# NvideaJetsonUSBPage2.net
KiCad netlist of a schematic drawn in Altium Designer
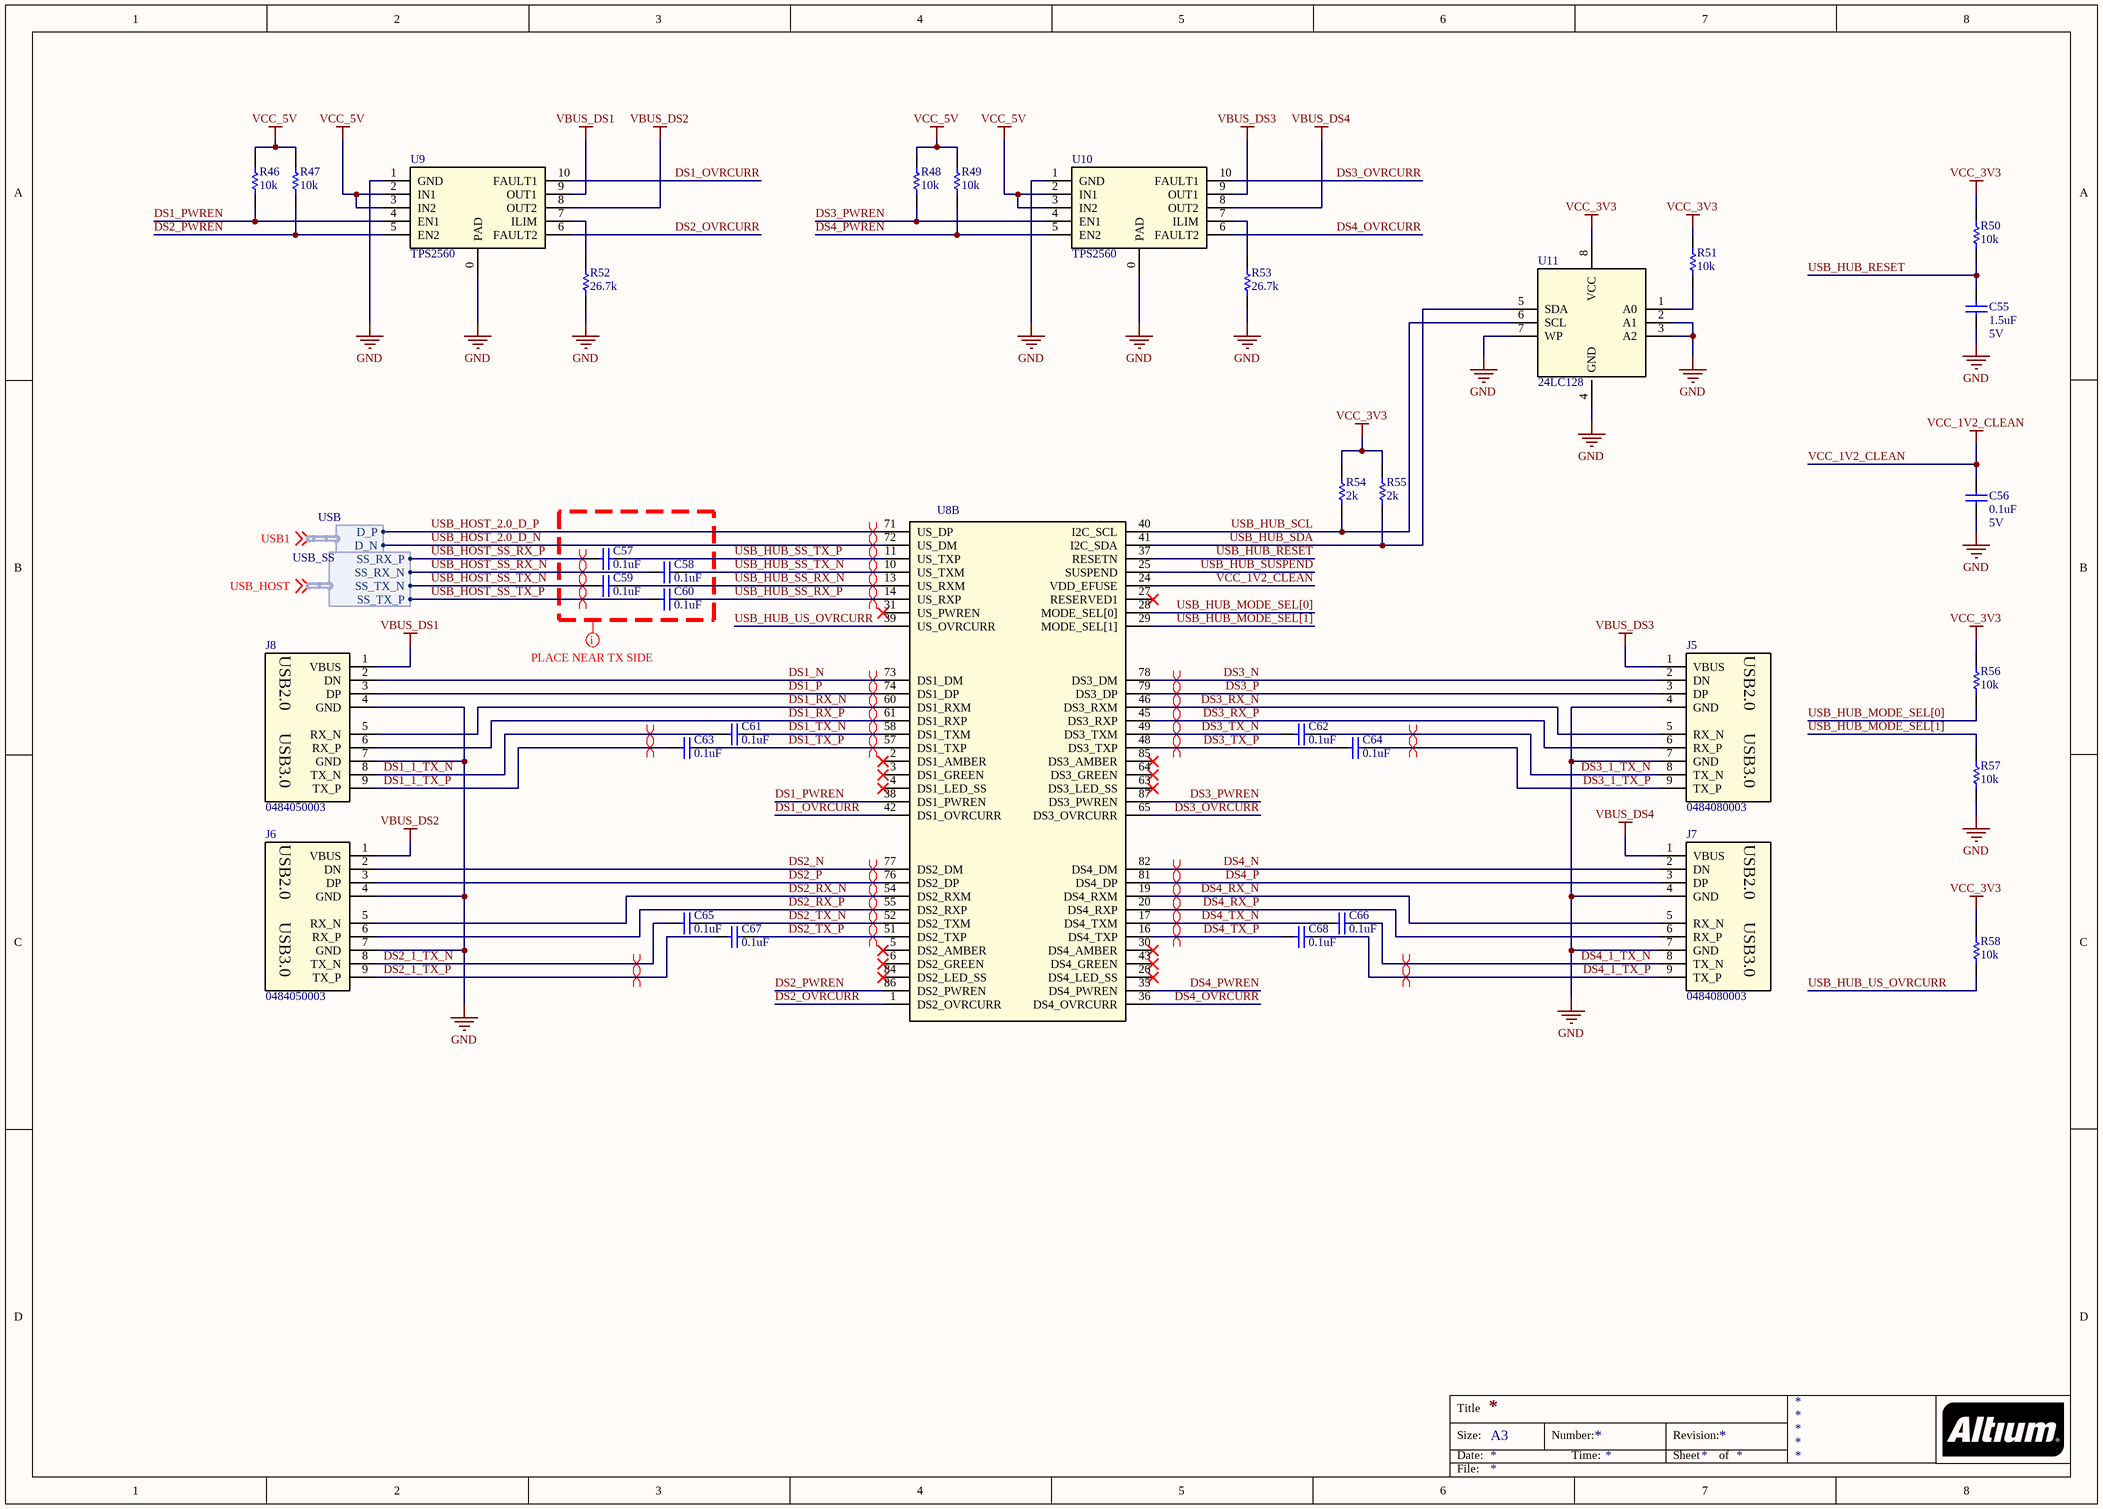
[diagram p0: NvideaJetsonUSBPage2.SchDoc]

(export (version "E")
  (design (tool "Eeschema 10.0.6"))
  (components
    (comp (ref "C55")
      (value "1.5uF")
      (footprint "C0402")
      (description "=Description")
      (fields (field (name "VOLTAGE") "5V") (field (name "Comment") "CAP"))
      (libsource (lib "DRClib") (part "CAP"))
    )
    (comp (ref "C56")
      (value "0.1uF")
      (footprint "C0402")
      (description "=Description")
      (fields (field (name "VOLTAGE") "5V") (field (name "Comment") "CAP"))
      (libsource (lib "DRClib") (part "CAP"))
    )
    (comp (ref "C57")
      (value "0.1uF")
      (footprint "C0402")
      (description "=Description")
      (fields (field (name "Comment") "CAP"))
      (libsource (lib "DRClib") (part "CAP"))
    )
    (comp (ref "C58")
      (value "0.1uF")
      (footprint "C0402")
      (description "=Description")
      (fields (field (name "Comment") "CAP"))
      (libsource (lib "DRClib") (part "CAP"))
    )
    (comp (ref "C59")
      (value "0.1uF")
      (footprint "C0402")
      (description "=Description")
      (fields (field (name "Comment") "CAP"))
      (libsource (lib "DRClib") (part "CAP"))
    )
    (comp (ref "C60")
      (value "0.1uF")
      (footprint "C0402")
      (description "=Description")
      (fields (field (name "Comment") "CAP"))
      (libsource (lib "DRClib") (part "CAP"))
    )
    (comp (ref "C61")
      (value "0.1uF")
      (footprint "C0402")
      (description "=Description")
      (fields (field (name "Comment") "CAP"))
      (libsource (lib "DRClib") (part "CAP"))
    )
    (comp (ref "C62")
      (value "0.1uF")
      (footprint "C0402")
      (description "=Description")
      (fields (field (name "Comment") "CAP"))
      (libsource (lib "DRClib") (part "CAP"))
    )
    (comp (ref "C63")
      (value "0.1uF")
      (footprint "C0402")
      (description "=Description")
      (fields (field (name "Comment") "CAP"))
      (libsource (lib "DRClib") (part "CAP"))
    )
    (comp (ref "C64")
      (value "0.1uF")
      (footprint "C0402")
      (description "=Description")
      (fields (field (name "Comment") "CAP"))
      (libsource (lib "DRClib") (part "CAP"))
    )
    (comp (ref "C65")
      (value "0.1uF")
      (footprint "C0402")
      (description "=Description")
      (fields (field (name "Comment") "CAP"))
      (libsource (lib "DRClib") (part "CAP"))
    )
    (comp (ref "C66")
      (value "0.1uF")
      (footprint "C0402")
      (description "=Description")
      (fields (field (name "Comment") "CAP"))
      (libsource (lib "DRClib") (part "CAP"))
    )
    (comp (ref "C67")
      (value "0.1uF")
      (footprint "C0402")
      (description "=Description")
      (fields (field (name "Comment") "CAP"))
      (libsource (lib "DRClib") (part "CAP"))
    )
    (comp (ref "C68")
      (value "0.1uF")
      (footprint "C0402")
      (description "=Description")
      (fields (field (name "Comment") "CAP"))
      (libsource (lib "DRClib") (part "CAP"))
    )
    (comp (ref "J5")
      (value "0484080003")
      (footprint "0484080003")
      (description "USB3.0 Recepticle Vertical")
      (libsource (lib "DRClib") (part "0484080003"))
    )
    (comp (ref "J6")
      (value "0484050003")
      (footprint "0484050003")
      (description "USB3.0 Recepticle Right Angle")
      (libsource (lib "DRClib") (part "0484050003"))
    )
    (comp (ref "J7")
      (value "0484080003")
      (footprint "0484080003")
      (description "USB3.0 Recepticle Vertical")
      (libsource (lib "DRClib") (part "0484080003"))
    )
    (comp (ref "J8")
      (value "0484050003")
      (footprint "0484050003")
      (description "USB3.0 Recepticle Right Angle")
      (libsource (lib "DRClib") (part "0484050003"))
    )
    (comp (ref "R46")
      (value "10k")
      (footprint "R0402")
      (description "=Description")
      (fields (field (name "Comment") "RES"))
      (libsource (lib "DRClib") (part "RES"))
    )
    (comp (ref "R47")
      (value "10k")
      (footprint "R0402")
      (description "=Description")
      (fields (field (name "Comment") "RES"))
      (libsource (lib "DRClib") (part "RES"))
    )
    (comp (ref "R48")
      (value "10k")
      (footprint "R0402")
      (description "=Description")
      (fields (field (name "Comment") "RES"))
      (libsource (lib "DRClib") (part "RES"))
    )
    (comp (ref "R49")
      (value "10k")
      (footprint "R0402")
      (description "=Description")
      (fields (field (name "Comment") "RES"))
      (libsource (lib "DRClib") (part "RES"))
    )
    (comp (ref "R50")
      (value "10k")
      (footprint "R0402")
      (description "=Description")
      (fields (field (name "Comment") "RES"))
      (libsource (lib "DRClib") (part "RES"))
    )
    (comp (ref "R51")
      (value "10k")
      (footprint "R0402")
      (description "=Description")
      (fields (field (name "Comment") "RES"))
      (libsource (lib "DRClib") (part "RES"))
    )
    (comp (ref "R52")
      (value "26.7k")
      (footprint "R0402")
      (description "=Description")
      (fields (field (name "Comment") "RES"))
      (libsource (lib "DRClib") (part "RES"))
    )
    (comp (ref "R53")
      (value "26.7k")
      (footprint "R0402")
      (description "=Description")
      (fields (field (name "Comment") "RES"))
      (libsource (lib "DRClib") (part "RES"))
    )
    (comp (ref "R54")
      (value "2k")
      (footprint "R0402")
      (description "=Description")
      (fields (field (name "Comment") "RES"))
      (libsource (lib "DRClib") (part "RES"))
    )
    (comp (ref "R55")
      (value "2k")
      (footprint "R0402")
      (description "=Description")
      (fields (field (name "Comment") "RES"))
      (libsource (lib "DRClib") (part "RES"))
    )
    (comp (ref "R56")
      (value "10k")
      (footprint "R0402")
      (description "=Description")
      (fields (field (name "Comment") "RES"))
      (libsource (lib "DRClib") (part "RES"))
    )
    (comp (ref "R57")
      (value "10k")
      (footprint "R0402")
      (description "=Description")
      (fields (field (name "Comment") "RES"))
      (libsource (lib "DRClib") (part "RES"))
    )
    (comp (ref "R58")
      (value "10k")
      (footprint "R0402")
      (description "=Description")
      (fields (field (name "Comment") "RES"))
      (libsource (lib "DRClib") (part "RES"))
    )
    (comp (ref "U8")
      (value "CYUSB3312-88LTXC")
      (footprint "QFN88")
      (description "USB3.0 Hub")
      (fields (field (name "MP") "2309411-2") (field (name "MF") "TE Connectivity"))
      (libsource (lib "DRClib") (part "CYUSB3312-88LTXC"))
    )
    (comp (ref "U9")
      (value "TPS2560")
      (footprint "VSON10")
      (description "IC PWR SWITCH N-CHAN 1:2 10VSON")
      (libsource (lib "DRClib") (part "TPS2560"))
    )
    (comp (ref "U10")
      (value "TPS2560")
      (footprint "VSON10")
      (description "IC PWR SWITCH N-CHAN 1:2 10VSON")
      (libsource (lib "DRClib") (part "TPS2560"))
    )
    (comp (ref "U11")
      (value "24LC128")
      (footprint "24LC128T-I/SN")
      (description "IC EEPROM 128K I2C 400KHZ")
      (libsource (lib "DRClib") (part "24LC128"))
    )
  )
  (nets
    (net (code "1") (name "/DS1_1_TX_N") (class "Default")
      (node (ref "C61") (pin "1") (pinfunction "1_1") (pintype "passive"))
      (node (ref "J8") (pin "8") (pinfunction "TX_N_8") (pintype "passive"))
    )
    (net (code "2") (name "/DS1_1_TX_P") (class "Default")
      (node (ref "C63") (pin "1") (pinfunction "1_1") (pintype "passive"))
      (node (ref "J8") (pin "9") (pinfunction "TX_P_9") (pintype "passive"))
    )
    (net (code "3") (name "/DS1_N") (class "Default")
      (node (ref "J8") (pin "2") (pinfunction "DN_2") (pintype "passive"))
      (node (ref "U8") (pin "73") (pinfunction "DS1_DM_73") (pintype "passive"))
    )
    (net (code "4") (name "/DS1_OVRCURR") (class "Default")
      (node (ref "U8") (pin "42") (pinfunction "DS1_OVRCURR_42") (pintype "passive"))
      (node (ref "U9") (pin "10") (pinfunction "FAULT1_10") (pintype "passive"))
    )
    (net (code "5") (name "/DS1_P") (class "Default")
      (node (ref "J8") (pin "3") (pinfunction "DP_3") (pintype "passive"))
      (node (ref "U8") (pin "74") (pinfunction "DS1_DP_74") (pintype "passive"))
    )
    (net (code "6") (name "/DS1_PWREN") (class "Default")
      (node (ref "R46") (pin "2") (pinfunction "2_2") (pintype "passive"))
      (node (ref "U8") (pin "38") (pinfunction "DS1_PWREN_38") (pintype "passive"))
      (node (ref "U9") (pin "4") (pinfunction "EN1_4") (pintype "passive"))
    )
    (net (code "7") (name "/DS1_RX_N") (class "Default")
      (node (ref "J8") (pin "5") (pinfunction "RX_N_5") (pintype "passive"))
      (node (ref "U8") (pin "60") (pinfunction "DS1_RXM_60") (pintype "passive"))
    )
    (net (code "8") (name "/DS1_RX_P") (class "Default")
      (node (ref "J8") (pin "6") (pinfunction "RX_P_6") (pintype "passive"))
      (node (ref "U8") (pin "61") (pinfunction "DS1_RXP_61") (pintype "passive"))
    )
    (net (code "9") (name "/DS1_TX_N") (class "Default")
      (node (ref "C61") (pin "2") (pinfunction "2_2") (pintype "passive"))
      (node (ref "U8") (pin "58") (pinfunction "DS1_TXM_58") (pintype "passive"))
    )
    (net (code "10") (name "/DS1_TX_P") (class "Default")
      (node (ref "C63") (pin "2") (pinfunction "2_2") (pintype "passive"))
      (node (ref "U8") (pin "57") (pinfunction "DS1_TXP_57") (pintype "passive"))
    )
    (net (code "11") (name "/DS2_1_TX_N") (class "Default")
      (node (ref "C65") (pin "1") (pinfunction "1_1") (pintype "passive"))
      (node (ref "J6") (pin "8") (pinfunction "TX_N_8") (pintype "passive"))
    )
    (net (code "12") (name "/DS2_1_TX_P") (class "Default")
      (node (ref "C67") (pin "1") (pinfunction "1_1") (pintype "passive"))
      (node (ref "J6") (pin "9") (pinfunction "TX_P_9") (pintype "passive"))
    )
    (net (code "13") (name "/DS2_N") (class "Default")
      (node (ref "J6") (pin "2") (pinfunction "DN_2") (pintype "passive"))
      (node (ref "U8") (pin "77") (pinfunction "DS2_DM_77") (pintype "passive"))
    )
    (net (code "14") (name "/DS2_OVRCURR") (class "Default")
      (node (ref "U8") (pin "1") (pinfunction "DS2_OVRCURR_1") (pintype "passive"))
      (node (ref "U9") (pin "6") (pinfunction "FAULT2_6") (pintype "passive"))
    )
    (net (code "15") (name "/DS2_P") (class "Default")
      (node (ref "J6") (pin "3") (pinfunction "DP_3") (pintype "passive"))
      (node (ref "U8") (pin "76") (pinfunction "DS2_DP_76") (pintype "passive"))
    )
    (net (code "16") (name "/DS2_PWREN") (class "Default")
      (node (ref "R47") (pin "2") (pinfunction "2_2") (pintype "passive"))
      (node (ref "U8") (pin "86") (pinfunction "DS2_PWREN_86") (pintype "passive"))
      (node (ref "U9") (pin "5") (pinfunction "EN2_5") (pintype "passive"))
    )
    (net (code "17") (name "/DS2_RX_N") (class "Default")
      (node (ref "J6") (pin "5") (pinfunction "RX_N_5") (pintype "passive"))
      (node (ref "U8") (pin "54") (pinfunction "DS2_RXM_54") (pintype "passive"))
    )
    (net (code "18") (name "/DS2_RX_P") (class "Default")
      (node (ref "J6") (pin "6") (pinfunction "RX_P_6") (pintype "passive"))
      (node (ref "U8") (pin "55") (pinfunction "DS2_RXP_55") (pintype "passive"))
    )
    (net (code "19") (name "/DS2_TX_N") (class "Default")
      (node (ref "C65") (pin "2") (pinfunction "2_2") (pintype "passive"))
      (node (ref "U8") (pin "52") (pinfunction "DS2_TXM_52") (pintype "passive"))
    )
    (net (code "20") (name "/DS2_TX_P") (class "Default")
      (node (ref "C67") (pin "2") (pinfunction "2_2") (pintype "passive"))
      (node (ref "U8") (pin "51") (pinfunction "DS2_TXP_51") (pintype "passive"))
    )
    (net (code "21") (name "/DS3_1_TX_N") (class "Default")
      (node (ref "C62") (pin "2") (pinfunction "2_2") (pintype "passive"))
      (node (ref "J5") (pin "8") (pinfunction "TX_N_8") (pintype "passive"))
    )
    (net (code "22") (name "/DS3_1_TX_P") (class "Default")
      (node (ref "C64") (pin "2") (pinfunction "2_2") (pintype "passive"))
      (node (ref "J5") (pin "9") (pinfunction "TX_P_9") (pintype "passive"))
    )
    (net (code "23") (name "/DS3_N") (class "Default")
      (node (ref "J5") (pin "2") (pinfunction "DN_2") (pintype "passive"))
      (node (ref "U8") (pin "78") (pinfunction "DS3_DM_78") (pintype "passive"))
    )
    (net (code "24") (name "/DS3_OVRCURR") (class "Default")
      (node (ref "U10") (pin "10") (pinfunction "FAULT1_10") (pintype "passive"))
      (node (ref "U8") (pin "65") (pinfunction "DS3_OVRCURR_65") (pintype "passive"))
    )
    (net (code "25") (name "/DS3_P") (class "Default")
      (node (ref "J5") (pin "3") (pinfunction "DP_3") (pintype "passive"))
      (node (ref "U8") (pin "79") (pinfunction "DS3_DP_79") (pintype "passive"))
    )
    (net (code "26") (name "/DS3_PWREN") (class "Default")
      (node (ref "R48") (pin "2") (pinfunction "2_2") (pintype "passive"))
      (node (ref "U10") (pin "4") (pinfunction "EN1_4") (pintype "passive"))
      (node (ref "U8") (pin "87") (pinfunction "DS3_PWREN_87") (pintype "passive"))
    )
    (net (code "27") (name "/DS3_RX_N") (class "Default")
      (node (ref "J5") (pin "5") (pinfunction "RX_N_5") (pintype "passive"))
      (node (ref "U8") (pin "46") (pinfunction "DS3_RXM_46") (pintype "passive"))
    )
    (net (code "28") (name "/DS3_RX_P") (class "Default")
      (node (ref "J5") (pin "6") (pinfunction "RX_P_6") (pintype "passive"))
      (node (ref "U8") (pin "45") (pinfunction "DS3_RXP_45") (pintype "passive"))
    )
    (net (code "29") (name "/DS3_TX_N") (class "Default")
      (node (ref "C62") (pin "1") (pinfunction "1_1") (pintype "passive"))
      (node (ref "U8") (pin "49") (pinfunction "DS3_TXM_49") (pintype "passive"))
    )
    (net (code "30") (name "/DS3_TX_P") (class "Default")
      (node (ref "C64") (pin "1") (pinfunction "1_1") (pintype "passive"))
      (node (ref "U8") (pin "48") (pinfunction "DS3_TXP_48") (pintype "passive"))
    )
    (net (code "31") (name "/DS4_1_TX_N") (class "Default")
      (node (ref "C66") (pin "2") (pinfunction "2_2") (pintype "passive"))
      (node (ref "J7") (pin "8") (pinfunction "TX_N_8") (pintype "passive"))
    )
    (net (code "32") (name "/DS4_1_TX_P") (class "Default")
      (node (ref "C68") (pin "2") (pinfunction "2_2") (pintype "passive"))
      (node (ref "J7") (pin "9") (pinfunction "TX_P_9") (pintype "passive"))
    )
    (net (code "33") (name "/DS4_N") (class "Default")
      (node (ref "J7") (pin "2") (pinfunction "DN_2") (pintype "passive"))
      (node (ref "U8") (pin "82") (pinfunction "DS4_DM_82") (pintype "passive"))
    )
    (net (code "34") (name "/DS4_OVRCURR") (class "Default")
      (node (ref "U10") (pin "6") (pinfunction "FAULT2_6") (pintype "passive"))
      (node (ref "U8") (pin "36") (pinfunction "DS4_OVRCURR_36") (pintype "passive"))
    )
    (net (code "35") (name "/DS4_P") (class "Default")
      (node (ref "J7") (pin "3") (pinfunction "DP_3") (pintype "passive"))
      (node (ref "U8") (pin "81") (pinfunction "DS4_DP_81") (pintype "passive"))
    )
    (net (code "36") (name "/DS4_PWREN") (class "Default")
      (node (ref "R49") (pin "2") (pinfunction "2_2") (pintype "passive"))
      (node (ref "U10") (pin "5") (pinfunction "EN2_5") (pintype "passive"))
      (node (ref "U8") (pin "35") (pinfunction "DS4_PWREN_35") (pintype "passive"))
    )
    (net (code "37") (name "/DS4_RX_N") (class "Default")
      (node (ref "J7") (pin "5") (pinfunction "RX_N_5") (pintype "passive"))
      (node (ref "U8") (pin "19") (pinfunction "DS4_RXM_19") (pintype "passive"))
    )
    (net (code "38") (name "/DS4_RX_P") (class "Default")
      (node (ref "J7") (pin "6") (pinfunction "RX_P_6") (pintype "passive"))
      (node (ref "U8") (pin "20") (pinfunction "DS4_RXP_20") (pintype "passive"))
    )
    (net (code "39") (name "/DS4_TX_N") (class "Default")
      (node (ref "C66") (pin "1") (pinfunction "1_1") (pintype "passive"))
      (node (ref "U8") (pin "17") (pinfunction "DS4_TXM_17") (pintype "passive"))
    )
    (net (code "40") (name "/DS4_TX_P") (class "Default")
      (node (ref "C68") (pin "1") (pinfunction "1_1") (pintype "passive"))
      (node (ref "U8") (pin "16") (pinfunction "DS4_TXP_16") (pintype "passive"))
    )
    (net (code "41") (name "/USB_HOST_2.0_D_N") (class "Default")
      (node (ref "U8") (pin "72") (pinfunction "US_DM_72") (pintype "passive"))
    )
    (net (code "42") (name "/USB_HOST_2.0_D_P") (class "Default")
      (node (ref "U8") (pin "71") (pinfunction "US_DP_71") (pintype "passive"))
    )
    (net (code "43") (name "/USB_HOST_SS_RX_N") (class "Default")
      (node (ref "C58") (pin "1") (pinfunction "1_1") (pintype "passive"))
    )
    (net (code "44") (name "/USB_HOST_SS_RX_P") (class "Default")
      (node (ref "C57") (pin "1") (pinfunction "1_1") (pintype "passive"))
    )
    (net (code "45") (name "/USB_HOST_SS_TX_N") (class "Default")
      (node (ref "C59") (pin "1") (pinfunction "1_1") (pintype "passive"))
    )
    (net (code "46") (name "/USB_HOST_SS_TX_P") (class "Default")
      (node (ref "C60") (pin "1") (pinfunction "1_1") (pintype "passive"))
    )
    (net (code "47") (name "/USB_HUB_MODE_SEL[0]") (class "Default")
      (node (ref "R56") (pin "2") (pinfunction "2_2") (pintype "passive"))
      (node (ref "U8") (pin "28") (pinfunction "MODE_SEL[0]_28") (pintype "passive"))
    )
    (net (code "48") (name "/USB_HUB_MODE_SEL[1]") (class "Default")
      (node (ref "R57") (pin "1") (pinfunction "1_1") (pintype "passive"))
      (node (ref "U8") (pin "29") (pinfunction "MODE_SEL[1]_29") (pintype "passive"))
    )
    (net (code "49") (name "/USB_HUB_RESET") (class "Default")
      (node (ref "C55") (pin "1") (pinfunction "1_1") (pintype "passive"))
      (node (ref "R50") (pin "2") (pinfunction "2_2") (pintype "passive"))
      (node (ref "U8") (pin "37") (pinfunction "RESETN_37") (pintype "passive"))
    )
    (net (code "50") (name "/USB_HUB_SCL") (class "Default")
      (node (ref "R54") (pin "2") (pinfunction "2_2") (pintype "passive"))
      (node (ref "U11") (pin "6") (pinfunction "SCL_6") (pintype "passive"))
      (node (ref "U8") (pin "40") (pinfunction "I2C_SCL_40") (pintype "passive"))
    )
    (net (code "51") (name "/USB_HUB_SDA") (class "Default")
      (node (ref "R55") (pin "2") (pinfunction "2_2") (pintype "passive"))
      (node (ref "U11") (pin "5") (pinfunction "SDA_5") (pintype "passive"))
      (node (ref "U8") (pin "41") (pinfunction "I2C_SDA_41") (pintype "passive"))
    )
    (net (code "52") (name "/USB_HUB_SS_RX_N") (class "Default")
      (node (ref "C59") (pin "2") (pinfunction "2_2") (pintype "passive"))
      (node (ref "U8") (pin "13") (pinfunction "US_RXM_13") (pintype "passive"))
    )
    (net (code "53") (name "/USB_HUB_SS_RX_P") (class "Default")
      (node (ref "C60") (pin "2") (pinfunction "2_2") (pintype "passive"))
      (node (ref "U8") (pin "14") (pinfunction "US_RXP_14") (pintype "passive"))
    )
    (net (code "54") (name "/USB_HUB_SS_TX_N") (class "Default")
      (node (ref "C58") (pin "2") (pinfunction "2_2") (pintype "passive"))
      (node (ref "U8") (pin "10") (pinfunction "US_TXM_10") (pintype "passive"))
    )
    (net (code "55") (name "/USB_HUB_SS_TX_P") (class "Default")
      (node (ref "C57") (pin "2") (pinfunction "2_2") (pintype "passive"))
      (node (ref "U8") (pin "11") (pinfunction "US_TXP_11") (pintype "passive"))
    )
    (net (code "56") (name "/USB_HUB_SUSPEND") (class "Default")
      (node (ref "U8") (pin "25") (pinfunction "SUSPEND_25") (pintype "passive"))
    )
    (net (code "57") (name "/USB_HUB_US_OVRCURR") (class "Default")
      (node (ref "R58") (pin "2") (pinfunction "2_2") (pintype "passive"))
      (node (ref "U8") (pin "39") (pinfunction "US_OVRCURR_39") (pintype "passive"))
    )
    (net (code "58") (name "GND") (class "Default")
      (node (ref "C55") (pin "2") (pinfunction "2_2") (pintype "passive"))
      (node (ref "C56") (pin "2") (pinfunction "2_2") (pintype "passive"))
      (node (ref "J5") (pin "4") (pinfunction "GND_4") (pintype "passive"))
      (node (ref "J5") (pin "7") (pinfunction "GND_7") (pintype "passive"))
      (node (ref "J6") (pin "4") (pinfunction "GND_4") (pintype "passive"))
      (node (ref "J6") (pin "7") (pinfunction "GND_7") (pintype "passive"))
      (node (ref "J7") (pin "4") (pinfunction "GND_4") (pintype "passive"))
      (node (ref "J7") (pin "7") (pinfunction "GND_7") (pintype "passive"))
      (node (ref "J8") (pin "4") (pinfunction "GND_4") (pintype "passive"))
      (node (ref "J8") (pin "7") (pinfunction "GND_7") (pintype "passive"))
      (node (ref "R52") (pin "2") (pinfunction "2_2") (pintype "passive"))
      (node (ref "R53") (pin "2") (pinfunction "2_2") (pintype "passive"))
      (node (ref "R57") (pin "2") (pinfunction "2_2") (pintype "passive"))
      (node (ref "U10") (pin "0") (pinfunction "PAD_0") (pintype "passive"))
      (node (ref "U10") (pin "1") (pinfunction "GND_1") (pintype "passive"))
      (node (ref "U11") (pin "2") (pinfunction "A1_2") (pintype "passive"))
      (node (ref "U11") (pin "3") (pinfunction "A2_3") (pintype "passive"))
      (node (ref "U11") (pin "4") (pinfunction "GND_4") (pintype "passive"))
      (node (ref "U11") (pin "7") (pinfunction "WP_7") (pintype "passive"))
      (node (ref "U9") (pin "0") (pinfunction "PAD_0") (pintype "passive"))
      (node (ref "U9") (pin "1") (pinfunction "GND_1") (pintype "passive"))
    )
    (net (code "59") (name "Net-(U9-ILIM)") (class "Default")
      (node (ref "R52") (pin "1") (pinfunction "1_1") (pintype "passive"))
      (node (ref "U9") (pin "7") (pinfunction "ILIM_7") (pintype "passive"))
    )
    (net (code "60") (name "Net-(U10-ILIM)") (class "Default")
      (node (ref "R53") (pin "1") (pinfunction "1_1") (pintype "passive"))
      (node (ref "U10") (pin "7") (pinfunction "ILIM_7") (pintype "passive"))
    )
    (net (code "61") (name "Net-(U11-A0)") (class "Default")
      (node (ref "R51") (pin "2") (pinfunction "2_2") (pintype "passive"))
      (node (ref "U11") (pin "1") (pinfunction "A0_1") (pintype "passive"))
    )
    (net (code "64") (name "VBUS_DS1") (class "Default")
      (node (ref "J8") (pin "1") (pinfunction "VBUS_1") (pintype "passive"))
      (node (ref "U9") (pin "9") (pinfunction "OUT1_9") (pintype "passive"))
    )
    (net (code "65") (name "VBUS_DS2") (class "Default")
      (node (ref "J6") (pin "1") (pinfunction "VBUS_1") (pintype "passive"))
      (node (ref "U9") (pin "8") (pinfunction "OUT2_8") (pintype "passive"))
    )
    (net (code "66") (name "VBUS_DS3") (class "Default")
      (node (ref "J5") (pin "1") (pinfunction "VBUS_1") (pintype "passive"))
      (node (ref "U10") (pin "9") (pinfunction "OUT1_9") (pintype "passive"))
    )
    (net (code "67") (name "VBUS_DS4") (class "Default")
      (node (ref "J7") (pin "1") (pinfunction "VBUS_1") (pintype "passive"))
      (node (ref "U10") (pin "8") (pinfunction "OUT2_8") (pintype "passive"))
    )
    (net (code "68") (name "VCC_1V2_CLEAN") (class "Default")
      (node (ref "C56") (pin "1") (pinfunction "1_1") (pintype "passive"))
      (node (ref "U8") (pin "24") (pinfunction "VDD_EFUSE_24") (pintype "passive"))
    )
    (net (code "69") (name "VCC_3V3") (class "Default")
      (node (ref "R50") (pin "1") (pinfunction "1_1") (pintype "passive"))
      (node (ref "R51") (pin "1") (pinfunction "1_1") (pintype "passive"))
      (node (ref "R54") (pin "1") (pinfunction "1_1") (pintype "passive"))
      (node (ref "R55") (pin "1") (pinfunction "1_1") (pintype "passive"))
      (node (ref "R56") (pin "1") (pinfunction "1_1") (pintype "passive"))
      (node (ref "R58") (pin "1") (pinfunction "1_1") (pintype "passive"))
      (node (ref "U11") (pin "8") (pinfunction "VCC_8") (pintype "passive"))
    )
    (net (code "70") (name "VCC_5V") (class "Default")
      (node (ref "R46") (pin "1") (pinfunction "1_1") (pintype "passive"))
      (node (ref "R47") (pin "1") (pinfunction "1_1") (pintype "passive"))
      (node (ref "R48") (pin "1") (pinfunction "1_1") (pintype "passive"))
      (node (ref "R49") (pin "1") (pinfunction "1_1") (pintype "passive"))
      (node (ref "U10") (pin "2") (pinfunction "IN1_2") (pintype "passive"))
      (node (ref "U10") (pin "3") (pinfunction "IN2_3") (pintype "passive"))
      (node (ref "U9") (pin "2") (pinfunction "IN1_2") (pintype "passive"))
      (node (ref "U9") (pin "3") (pinfunction "IN2_3") (pintype "passive"))
    )
    (net (code "71") (name "unconnected-(U8B-DS1_AMBER-Pad2)") (class "Default")
      (node (ref "U8") (pin "2") (pinfunction "DS1_AMBER_2") (pintype "passive+no_connect"))
    )
    (net (code "72") (name "unconnected-(U8B-DS1_GREEN-Pad3)") (class "Default")
      (node (ref "U8") (pin "3") (pinfunction "DS1_GREEN_3") (pintype "passive+no_connect"))
    )
    (net (code "73") (name "unconnected-(U8B-DS1_LED_SS-Pad4)") (class "Default")
      (node (ref "U8") (pin "4") (pinfunction "DS1_LED_SS_4") (pintype "passive+no_connect"))
    )
    (net (code "74") (name "unconnected-(U8B-DS2_AMBER-Pad5)") (class "Default")
      (node (ref "U8") (pin "5") (pinfunction "DS2_AMBER_5") (pintype "passive+no_connect"))
    )
    (net (code "75") (name "unconnected-(U8B-DS2_GREEN-Pad6)") (class "Default")
      (node (ref "U8") (pin "6") (pinfunction "DS2_GREEN_6") (pintype "passive+no_connect"))
    )
    (net (code "76") (name "unconnected-(U8B-DS2_LED_SS-Pad84)") (class "Default")
      (node (ref "U8") (pin "84") (pinfunction "DS2_LED_SS_84") (pintype "passive+no_connect"))
    )
    (net (code "77") (name "unconnected-(U8B-DS3_AMBER-Pad85)") (class "Default")
      (node (ref "U8") (pin "85") (pinfunction "DS3_AMBER_85") (pintype "passive+no_connect"))
    )
    (net (code "78") (name "unconnected-(U8B-DS3_GREEN-Pad64)") (class "Default")
      (node (ref "U8") (pin "64") (pinfunction "DS3_GREEN_64") (pintype "passive+no_connect"))
    )
    (net (code "79") (name "unconnected-(U8B-DS3_LED_SS-Pad63)") (class "Default")
      (node (ref "U8") (pin "63") (pinfunction "DS3_LED_SS_63") (pintype "passive+no_connect"))
    )
    (net (code "80") (name "unconnected-(U8B-DS4_AMBER-Pad30)") (class "Default")
      (node (ref "U8") (pin "30") (pinfunction "DS4_AMBER_30") (pintype "passive+no_connect"))
    )
    (net (code "81") (name "unconnected-(U8B-DS4_GREEN-Pad43)") (class "Default")
      (node (ref "U8") (pin "43") (pinfunction "DS4_GREEN_43") (pintype "passive+no_connect"))
    )
    (net (code "82") (name "unconnected-(U8B-DS4_LED_SS-Pad26)") (class "Default")
      (node (ref "U8") (pin "26") (pinfunction "DS4_LED_SS_26") (pintype "passive+no_connect"))
    )
    (net (code "83") (name "unconnected-(U8B-RESERVED1-Pad27)") (class "Default")
      (node (ref "U8") (pin "27") (pinfunction "RESERVED1_27") (pintype "passive+no_connect"))
    )
    (net (code "84") (name "unconnected-(U8B-US_PWREN-Pad31)") (class "Default")
      (node (ref "U8") (pin "31") (pinfunction "US_PWREN_31") (pintype "passive+no_connect"))
    )
  )
)
